# Slave_V0_1.net
KiCad netlist of a schematic drawn in EAGLE
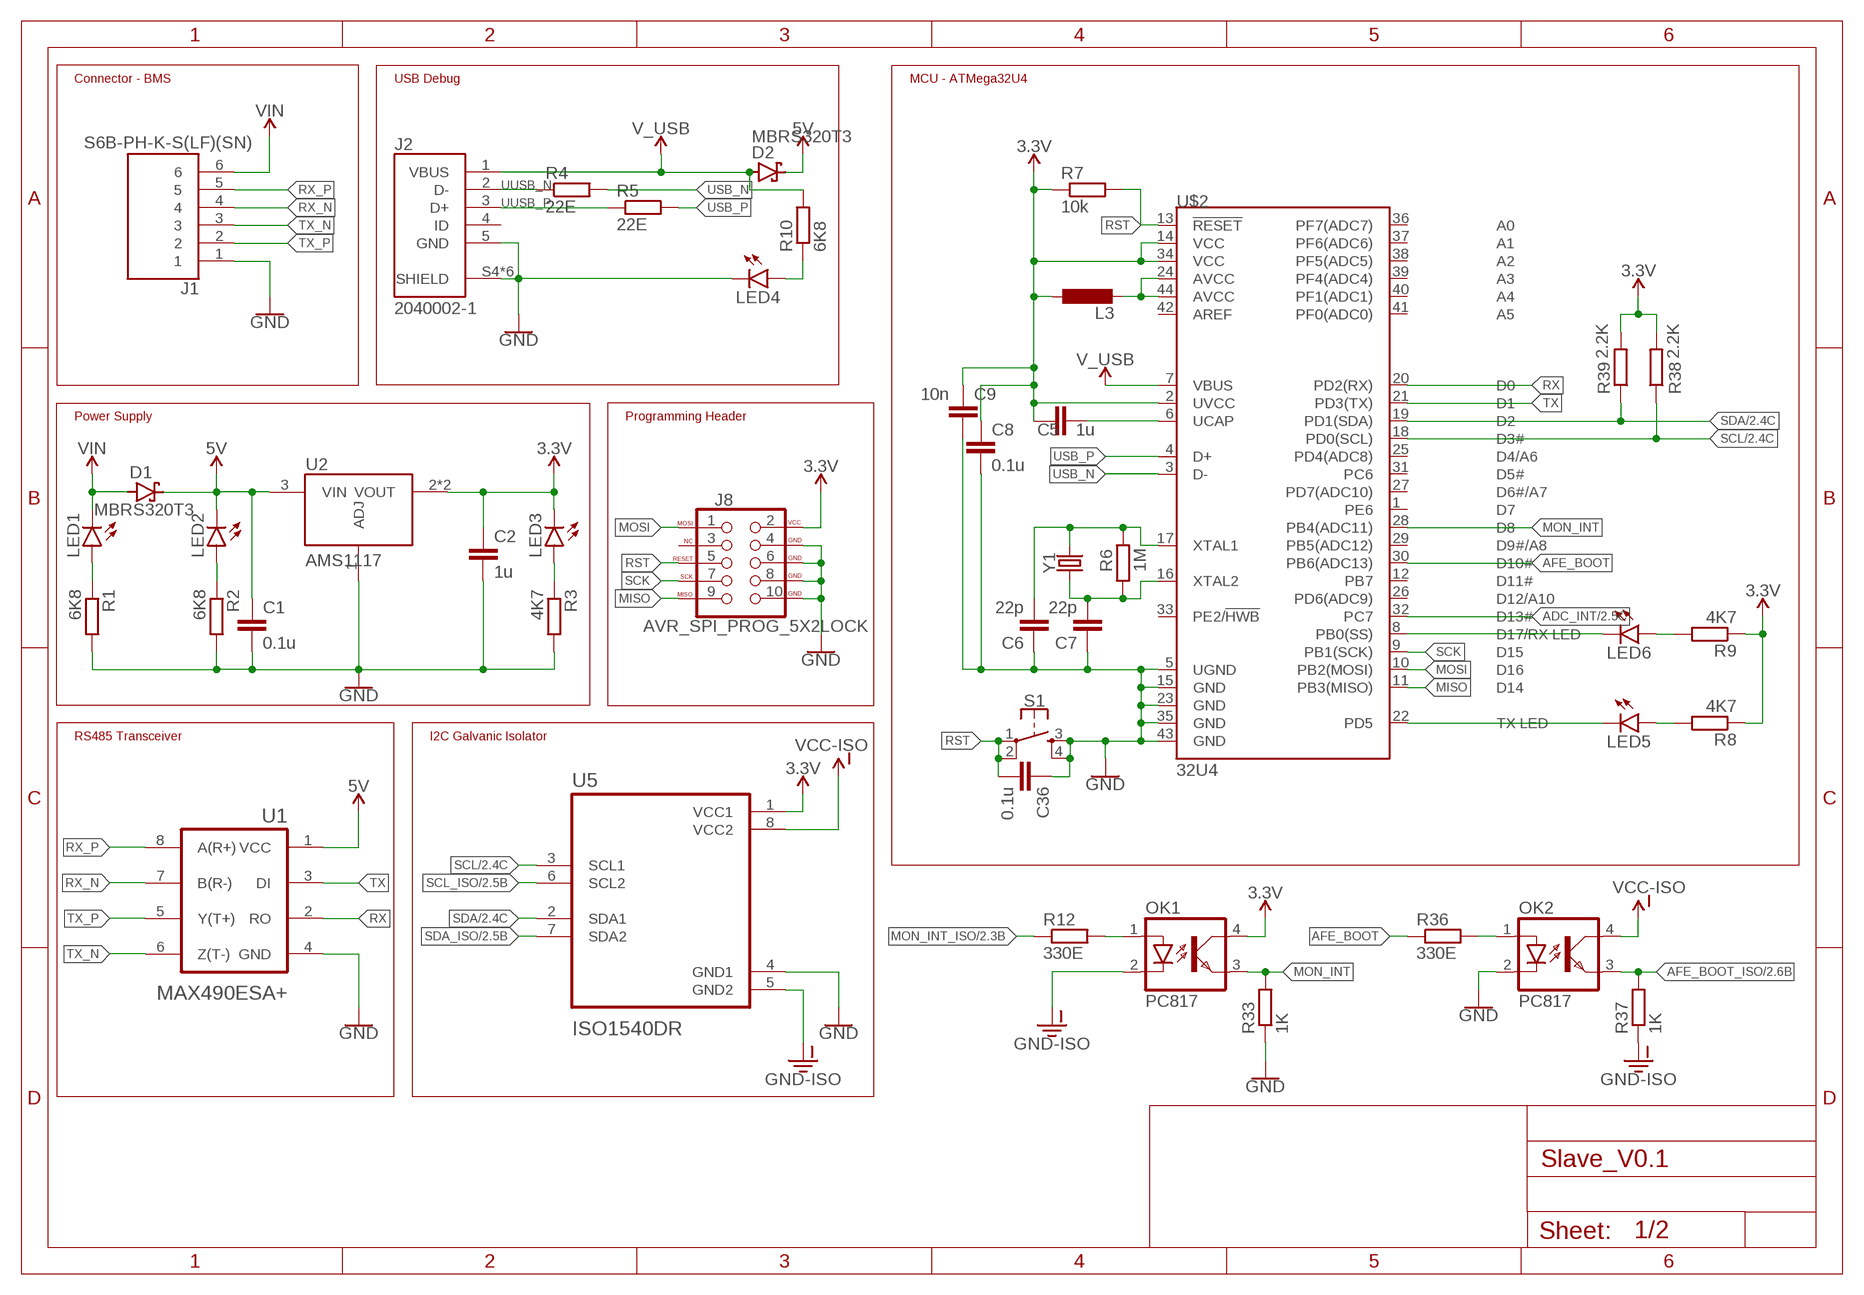
[diagram p0: schematic, sheet 1]
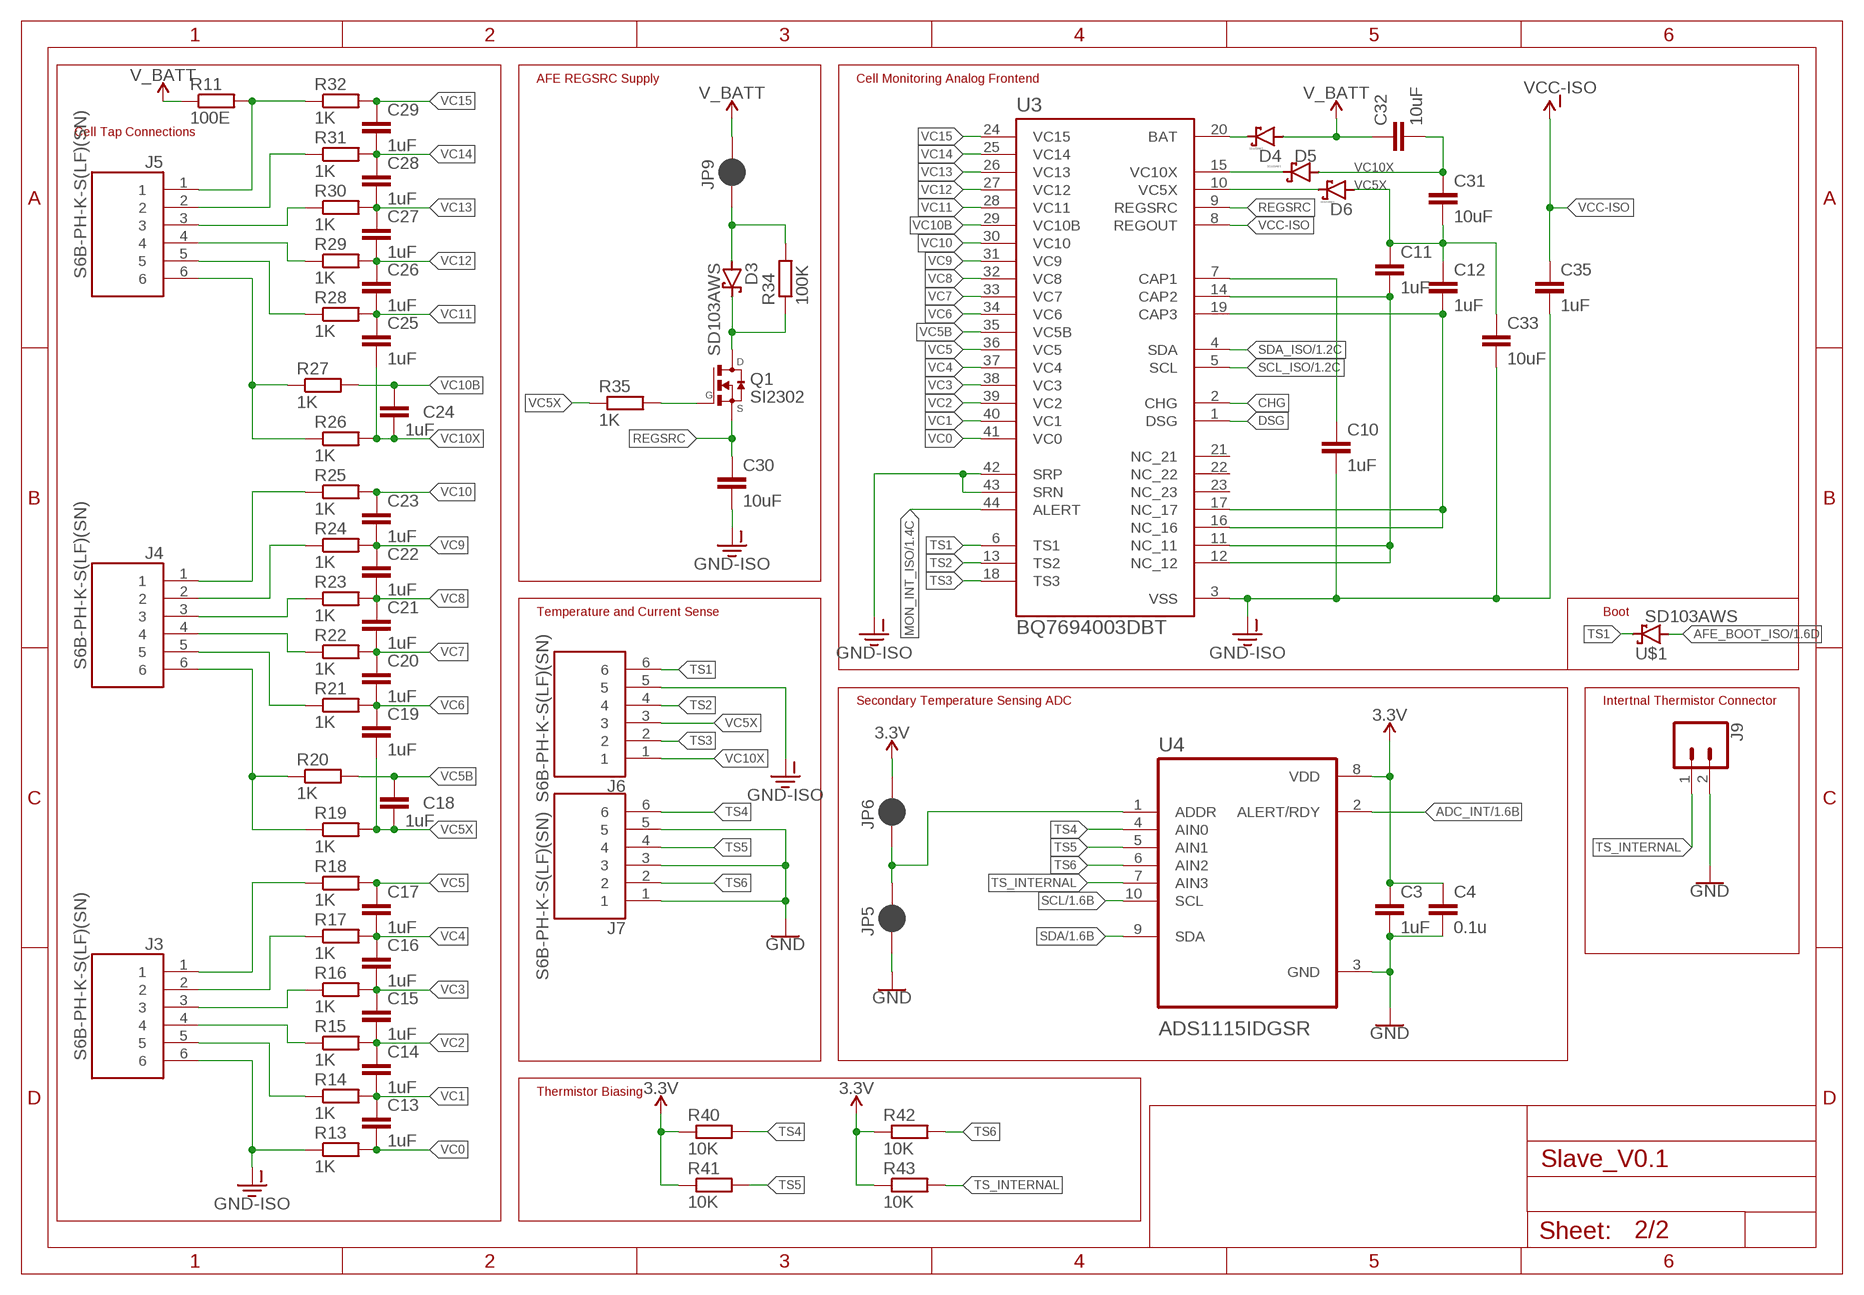
[diagram p1: schematic, sheet 2]

(export (version "E")
  (design (tool "Eeschema 10.0.6"))
  (components
    (comp (ref "C3")
      (value "1uF")
      (footprint "eagle-import:C0805K")
      (libsource (lib "eagle-import") (part "C-EUC0805K"))
    )
    (comp (ref "C4")
      (value "0.1u")
      (footprint "eagle-import:C0805K")
      (libsource (lib "eagle-import") (part "C-EUC0805K"))
    )
    (comp (ref "C10")
      (value "1uF")
      (footprint "eagle-import:C0805")
      (libsource (lib "eagle-import") (part "C-EUC0805"))
    )
    (comp (ref "C11")
      (value "1uF")
      (footprint "eagle-import:C0805")
      (libsource (lib "eagle-import") (part "C-EUC0805"))
    )
    (comp (ref "C12")
      (value "1uF")
      (footprint "eagle-import:C0805")
      (libsource (lib "eagle-import") (part "C-EUC0805"))
    )
    (comp (ref "C13")
      (value "1uF")
      (footprint "eagle-import:C0805")
      (libsource (lib "eagle-import") (part "C-EUC0805"))
    )
    (comp (ref "C14")
      (value "1uF")
      (footprint "eagle-import:C0805")
      (libsource (lib "eagle-import") (part "C-EUC0805"))
    )
    (comp (ref "C15")
      (value "1uF")
      (footprint "eagle-import:C0805")
      (libsource (lib "eagle-import") (part "C-EUC0805"))
    )
    (comp (ref "C16")
      (value "1uF")
      (footprint "eagle-import:C0805")
      (libsource (lib "eagle-import") (part "C-EUC0805"))
    )
    (comp (ref "C17")
      (value "1uF")
      (footprint "eagle-import:C0805")
      (libsource (lib "eagle-import") (part "C-EUC0805"))
    )
    (comp (ref "C18")
      (value "1uF")
      (footprint "eagle-import:C0805")
      (libsource (lib "eagle-import") (part "C-EUC0805"))
    )
    (comp (ref "C19")
      (value "1uF")
      (footprint "eagle-import:C0805")
      (libsource (lib "eagle-import") (part "C-EUC0805"))
    )
    (comp (ref "C20")
      (value "1uF")
      (footprint "eagle-import:C0805")
      (libsource (lib "eagle-import") (part "C-EUC0805"))
    )
    (comp (ref "C21")
      (value "1uF")
      (footprint "eagle-import:C0805")
      (libsource (lib "eagle-import") (part "C-EUC0805"))
    )
    (comp (ref "C22")
      (value "1uF")
      (footprint "eagle-import:C0805")
      (libsource (lib "eagle-import") (part "C-EUC0805"))
    )
    (comp (ref "C23")
      (value "1uF")
      (footprint "eagle-import:C0805")
      (libsource (lib "eagle-import") (part "C-EUC0805"))
    )
    (comp (ref "C24")
      (value "1uF")
      (footprint "eagle-import:C0805")
      (libsource (lib "eagle-import") (part "C-EUC0805"))
    )
    (comp (ref "C25")
      (value "1uF")
      (footprint "eagle-import:C0805")
      (libsource (lib "eagle-import") (part "C-EUC0805"))
    )
    (comp (ref "C26")
      (value "1uF")
      (footprint "eagle-import:C0805")
      (libsource (lib "eagle-import") (part "C-EUC0805"))
    )
    (comp (ref "C27")
      (value "1uF")
      (footprint "eagle-import:C0805")
      (libsource (lib "eagle-import") (part "C-EUC0805"))
    )
    (comp (ref "C28")
      (value "1uF")
      (footprint "eagle-import:C0805")
      (libsource (lib "eagle-import") (part "C-EUC0805"))
    )
    (comp (ref "C29")
      (value "1uF")
      (footprint "eagle-import:C0805")
      (libsource (lib "eagle-import") (part "C-EUC0805"))
    )
    (comp (ref "C30")
      (value "10uF")
      (footprint "eagle-import:C0805")
      (libsource (lib "eagle-import") (part "C-EUC0805"))
    )
    (comp (ref "C31")
      (value "10uF")
      (footprint "eagle-import:C0805")
      (libsource (lib "eagle-import") (part "C-EUC0805"))
    )
    (comp (ref "C32")
      (value "10uF")
      (footprint "eagle-import:C0805")
      (libsource (lib "eagle-import") (part "C-EUC0805"))
    )
    (comp (ref "C33")
      (value "10uF")
      (footprint "eagle-import:C0805")
      (libsource (lib "eagle-import") (part "C-EUC0805"))
    )
    (comp (ref "C35")
      (value "1uF")
      (footprint "eagle-import:C0805")
      (libsource (lib "eagle-import") (part "C-EUC0805"))
    )
    (comp (ref "D3")
      (value "SD103AWS")
      (footprint "eagle-import:SOD323_ST")
      (libsource (lib "eagle-import") (part "SD103AWS"))
    )
    (comp (ref "D4")
      (value "SD103AWS")
      (footprint "eagle-import:SOD323_ST")
      (libsource (lib "eagle-import") (part "SD103AWS"))
    )
    (comp (ref "D5")
      (value "SD103AWS")
      (footprint "eagle-import:SOD323_ST")
      (libsource (lib "eagle-import") (part "SD103AWS"))
    )
    (comp (ref "D6")
      (value "SD103AWS")
      (footprint "eagle-import:SOD323_ST")
      (libsource (lib "eagle-import") (part "SD103AWS"))
    )
    (comp (ref "J3")
      (value "S6B-PH-K-S(LF)(SN)")
      (footprint "eagle-import:JST_S6B-PH-K-S(LF)(SN)")
      (fields (field (name "MF") "JST Sales"))
      (libsource (lib "eagle-import") (part "S6B-PH-K-S(LF)(SN)"))
    )
    (comp (ref "J4")
      (value "S6B-PH-K-S(LF)(SN)")
      (footprint "eagle-import:JST_S6B-PH-K-S(LF)(SN)")
      (fields (field (name "MF") "JST Sales"))
      (libsource (lib "eagle-import") (part "S6B-PH-K-S(LF)(SN)"))
    )
    (comp (ref "J5")
      (value "S6B-PH-K-S(LF)(SN)")
      (footprint "eagle-import:JST_S6B-PH-K-S(LF)(SN)")
      (fields (field (name "MF") "JST Sales"))
      (libsource (lib "eagle-import") (part "S6B-PH-K-S(LF)(SN)"))
    )
    (comp (ref "J6")
      (value "S6B-PH-K-S(LF)(SN)")
      (footprint "eagle-import:JST_S6B-PH-K-S(LF)(SN)")
      (fields (field (name "MF") "JST Sales"))
      (libsource (lib "eagle-import") (part "S6B-PH-K-S(LF)(SN)"))
    )
    (comp (ref "J7")
      (value "S6B-PH-K-S(LF)(SN)")
      (footprint "eagle-import:JST_S6B-PH-K-S(LF)(SN)")
      (fields (field (name "MF") "JST Sales"))
      (libsource (lib "eagle-import") (part "S6B-PH-K-S(LF)(SN)"))
    )
    (comp (ref "J9")
      (value "CONN_023.5MM-NO_SILK")
      (footprint "eagle-import:SCREWTERMINAL-3.5MM-2-NS")
      (libsource (lib "eagle-import") (part "CONN_023.5MM-NO_SILK"))
    )
    (comp (ref "JP5")
      (value "JUMPER-SMT_2_NC_PASTE_SILK")
      (footprint "eagle-import:SMT-JUMPER_2_NC_PASTE_SILK")
      (libsource (lib "eagle-import") (part "JUMPER-SMT_2_NC_PASTE_SILK"))
    )
    (comp (ref "JP6")
      (value "JUMPER-SMT_2_NC_PASTE_SILK")
      (footprint "eagle-import:SMT-JUMPER_2_NC_PASTE_SILK")
      (libsource (lib "eagle-import") (part "JUMPER-SMT_2_NC_PASTE_SILK"))
    )
    (comp (ref "JP9")
      (value "JUMPER-SMT_2_NC_PASTE_SILK")
      (footprint "eagle-import:SMT-JUMPER_2_NC_PASTE_SILK")
      (libsource (lib "eagle-import") (part "JUMPER-SMT_2_NC_PASTE_SILK"))
    )
    (comp (ref "Q1")
      (value "SI2302")
      (footprint "eagle-import:SOT23")
      (fields (field (name "MF") "Vishay Siliconix"))
      (libsource (lib "eagle-import") (part "SI2302"))
    )
    (comp (ref "R11")
      (value "100E")
      (footprint "eagle-import:R0805")
      (libsource (lib "eagle-import") (part "R-EU_R0805"))
    )
    (comp (ref "R13")
      (value "1K")
      (footprint "eagle-import:R0805")
      (libsource (lib "eagle-import") (part "R-EU_R0805"))
    )
    (comp (ref "R14")
      (value "1K")
      (footprint "eagle-import:R0805")
      (libsource (lib "eagle-import") (part "R-EU_R0805"))
    )
    (comp (ref "R15")
      (value "1K")
      (footprint "eagle-import:R0805")
      (libsource (lib "eagle-import") (part "R-EU_R0805"))
    )
    (comp (ref "R16")
      (value "1K")
      (footprint "eagle-import:R0805")
      (libsource (lib "eagle-import") (part "R-EU_R0805"))
    )
    (comp (ref "R17")
      (value "1K")
      (footprint "eagle-import:R0805")
      (libsource (lib "eagle-import") (part "R-EU_R0805"))
    )
    (comp (ref "R18")
      (value "1K")
      (footprint "eagle-import:R0805")
      (libsource (lib "eagle-import") (part "R-EU_R0805"))
    )
    (comp (ref "R19")
      (value "1K")
      (footprint "eagle-import:R0805")
      (libsource (lib "eagle-import") (part "R-EU_R0805"))
    )
    (comp (ref "R20")
      (value "1K")
      (footprint "eagle-import:R0805")
      (libsource (lib "eagle-import") (part "R-EU_R0805"))
    )
    (comp (ref "R21")
      (value "1K")
      (footprint "eagle-import:R0805")
      (libsource (lib "eagle-import") (part "R-EU_R0805"))
    )
    (comp (ref "R22")
      (value "1K")
      (footprint "eagle-import:R0805")
      (libsource (lib "eagle-import") (part "R-EU_R0805"))
    )
    (comp (ref "R23")
      (value "1K")
      (footprint "eagle-import:R0805")
      (libsource (lib "eagle-import") (part "R-EU_R0805"))
    )
    (comp (ref "R24")
      (value "1K")
      (footprint "eagle-import:R0805")
      (libsource (lib "eagle-import") (part "R-EU_R0805"))
    )
    (comp (ref "R25")
      (value "1K")
      (footprint "eagle-import:R0805")
      (libsource (lib "eagle-import") (part "R-EU_R0805"))
    )
    (comp (ref "R26")
      (value "1K")
      (footprint "eagle-import:R0805")
      (libsource (lib "eagle-import") (part "R-EU_R0805"))
    )
    (comp (ref "R27")
      (value "1K")
      (footprint "eagle-import:R0805")
      (libsource (lib "eagle-import") (part "R-EU_R0805"))
    )
    (comp (ref "R28")
      (value "1K")
      (footprint "eagle-import:R0805")
      (libsource (lib "eagle-import") (part "R-EU_R0805"))
    )
    (comp (ref "R29")
      (value "1K")
      (footprint "eagle-import:R0805")
      (libsource (lib "eagle-import") (part "R-EU_R0805"))
    )
    (comp (ref "R30")
      (value "1K")
      (footprint "eagle-import:R0805")
      (libsource (lib "eagle-import") (part "R-EU_R0805"))
    )
    (comp (ref "R31")
      (value "1K")
      (footprint "eagle-import:R0805")
      (libsource (lib "eagle-import") (part "R-EU_R0805"))
    )
    (comp (ref "R32")
      (value "1K")
      (footprint "eagle-import:R0805")
      (libsource (lib "eagle-import") (part "R-EU_R0805"))
    )
    (comp (ref "R34")
      (value "100K")
      (footprint "eagle-import:R0805")
      (libsource (lib "eagle-import") (part "R-EU_R0805"))
    )
    (comp (ref "R35")
      (value "1K")
      (footprint "eagle-import:R0805")
      (libsource (lib "eagle-import") (part "R-EU_R0805"))
    )
    (comp (ref "R40")
      (value "10K")
      (footprint "eagle-import:R0805")
      (libsource (lib "eagle-import") (part "R-EU_R0805"))
    )
    (comp (ref "R41")
      (value "10K")
      (footprint "eagle-import:R0805")
      (libsource (lib "eagle-import") (part "R-EU_R0805"))
    )
    (comp (ref "R42")
      (value "10K")
      (footprint "eagle-import:R0805")
      (libsource (lib "eagle-import") (part "R-EU_R0805"))
    )
    (comp (ref "R43")
      (value "10K")
      (footprint "eagle-import:R0805")
      (libsource (lib "eagle-import") (part "R-EU_R0805"))
    )
    (comp (ref "U$1")
      (value "SD103AWS")
      (footprint "eagle-import:SOD323_ST")
      (libsource (lib "eagle-import") (part "SD103AWS"))
    )
    (comp (ref "U3")
      (value "BQ7694003DBT")
      (footprint "eagle-import:SOP50P640X120-44N")
      (fields (field (name "MF") "Texas Instruments"))
      (libsource (lib "eagle-import") (part "BQ7694003DBT"))
    )
    (comp (ref "U4")
      (value "ADS1115IDGSR")
      (footprint "eagle-import:SOP50P490X110-10N")
      (fields (field (name "MF") "Texas Instruments"))
      (libsource (lib "eagle-import") (part "ADS1115IDGSR"))
    )
    (comp (ref "C1")
      (value "0.1u")
      (footprint "eagle-import:C0805")
      (libsource (lib "eagle-import") (part "C-EUC0805"))
    )
    (comp (ref "C2")
      (value "1u")
      (footprint "eagle-import:C0805")
      (libsource (lib "eagle-import") (part "C-EUC0805"))
    )
    (comp (ref "C5")
      (value "1u")
      (footprint "eagle-import:C0805")
      (libsource (lib "eagle-import") (part "C-EUC0805"))
    )
    (comp (ref "C6")
      (value "22p")
      (footprint "eagle-import:C0805")
      (libsource (lib "eagle-import") (part "C-EUC0805"))
    )
    (comp (ref "C7")
      (value "22p")
      (footprint "eagle-import:C0805")
      (libsource (lib "eagle-import") (part "C-EUC0805"))
    )
    (comp (ref "C8")
      (value "0.1u")
      (footprint "eagle-import:C0805")
      (libsource (lib "eagle-import") (part "C-EUC0805"))
    )
    (comp (ref "C9")
      (value "10n")
      (footprint "eagle-import:C0805")
      (libsource (lib "eagle-import") (part "C-EUC0805"))
    )
    (comp (ref "C36")
      (value "0.1u")
      (footprint "eagle-import:C0805")
      (libsource (lib "eagle-import") (part "C-EUC0805"))
    )
    (comp (ref "D1")
      (value "MBRS320T3")
      (footprint "eagle-import:SMC")
      (libsource (lib "eagle-import") (part "MBRS30T32"))
    )
    (comp (ref "D2")
      (value "MBRS320T3")
      (footprint "eagle-import:SMC")
      (libsource (lib "eagle-import") (part "MBRS30T32"))
    )
    (comp (ref "J1")
      (value "S6B-PH-K-S(LF)(SN)")
      (footprint "eagle-import:JST_S6B-PH-K-S(LF)(SN)")
      (fields (field (name "MF") "JST Sales"))
      (libsource (lib "eagle-import") (part "S6B-PH-K-S(LF)(SN)"))
    )
    (comp (ref "J2")
      (value "2040002-1")
      (footprint "eagle-import:TE_2040002-1")
      (fields (field (name "MF") "TE Connectivity"))
      (libsource (lib "eagle-import") (part "2040002-1"))
    )
    (comp (ref "J8")
      (value "AVR_SPI_PROG_5X2LOCK")
      (footprint "eagle-import:2X5-SHROUDED_LOCK")
      (libsource (lib "eagle-import") (part "AVR_SPI_PROG_5X2LOCK"))
    )
    (comp (ref "L3")
      (value "L-EUL2012C")
      (footprint "eagle-import:L2012C")
      (libsource (lib "eagle-import") (part "L-EUL2012C"))
    )
    (comp (ref "LED1")
      (value "LEDCHIPLED_0805")
      (footprint "eagle-import:CHIPLED_0805")
      (libsource (lib "eagle-import") (part "LEDCHIPLED_0805"))
    )
    (comp (ref "LED2")
      (value "LEDCHIPLED_0805")
      (footprint "eagle-import:CHIPLED_0805")
      (libsource (lib "eagle-import") (part "LEDCHIPLED_0805"))
    )
    (comp (ref "LED3")
      (value "LEDCHIPLED_0805")
      (footprint "eagle-import:CHIPLED_0805")
      (libsource (lib "eagle-import") (part "LEDCHIPLED_0805"))
    )
    (comp (ref "LED4")
      (value "LEDCHIPLED_0805")
      (footprint "eagle-import:CHIPLED_0805")
      (libsource (lib "eagle-import") (part "LEDCHIPLED_0805"))
    )
    (comp (ref "LED5")
      (value "LEDCHIPLED_0805")
      (footprint "eagle-import:CHIPLED_0805")
      (libsource (lib "eagle-import") (part "LEDCHIPLED_0805"))
    )
    (comp (ref "LED6")
      (value "LEDCHIPLED_0805")
      (footprint "eagle-import:CHIPLED_0805")
      (libsource (lib "eagle-import") (part "LEDCHIPLED_0805"))
    )
    (comp (ref "OK1")
      (value "PC817")
      (footprint "eagle-import:DIL04")
      (fields (field (name "MPN") "PC817X4J000F"))
      (libsource (lib "eagle-import") (part "PC817"))
    )
    (comp (ref "OK2")
      (value "PC817")
      (footprint "eagle-import:DIL04")
      (fields (field (name "MPN") "PC817X4J000F"))
      (libsource (lib "eagle-import") (part "PC817"))
    )
    (comp (ref "R1")
      (value "6K8")
      (footprint "eagle-import:R0805")
      (libsource (lib "eagle-import") (part "R-EU_R0805"))
    )
    (comp (ref "R2")
      (value "6K8")
      (footprint "eagle-import:R0805")
      (libsource (lib "eagle-import") (part "R-EU_R0805"))
    )
    (comp (ref "R3")
      (value "4K7")
      (footprint "eagle-import:R0805")
      (libsource (lib "eagle-import") (part "R-EU_R0805"))
    )
    (comp (ref "R4")
      (value "22E")
      (footprint "eagle-import:R0805")
      (libsource (lib "eagle-import") (part "R-EU_R0805"))
    )
    (comp (ref "R5")
      (value "22E")
      (footprint "eagle-import:R0805")
      (libsource (lib "eagle-import") (part "R-EU_R0805"))
    )
    (comp (ref "R6")
      (value "1M")
      (footprint "eagle-import:R0805")
      (libsource (lib "eagle-import") (part "R-EU_R0805"))
    )
    (comp (ref "R7")
      (value "10k")
      (footprint "eagle-import:R0805")
      (libsource (lib "eagle-import") (part "R-EU_R0805"))
    )
    (comp (ref "R8")
      (value "4K7")
      (footprint "eagle-import:R0805")
      (libsource (lib "eagle-import") (part "R-EU_R0805"))
    )
    (comp (ref "R9")
      (value "4K7")
      (footprint "eagle-import:R0805")
      (libsource (lib "eagle-import") (part "R-EU_R0805"))
    )
    (comp (ref "R10")
      (value "6K8")
      (footprint "eagle-import:R0805")
      (libsource (lib "eagle-import") (part "R-EU_R0805"))
    )
    (comp (ref "R12")
      (value "330E")
      (footprint "eagle-import:R0805")
      (libsource (lib "eagle-import") (part "R-EU_R0805"))
    )
    (comp (ref "R33")
      (value "1K")
      (footprint "eagle-import:R0805")
      (libsource (lib "eagle-import") (part "R-EU_R0805"))
    )
    (comp (ref "R36")
      (value "330E")
      (footprint "eagle-import:R0805")
      (libsource (lib "eagle-import") (part "R-EU_R0805"))
    )
    (comp (ref "R37")
      (value "1K")
      (footprint "eagle-import:R0805")
      (libsource (lib "eagle-import") (part "R-EU_R0805"))
    )
    (comp (ref "R38")
      (value "2.2K")
      (footprint "eagle-import:R0805")
      (libsource (lib "eagle-import") (part "R-EU_R0805"))
    )
    (comp (ref "R39")
      (value "2.2K")
      (footprint "eagle-import:R0805")
      (libsource (lib "eagle-import") (part "R-EU_R0805"))
    )
    (comp (ref "S1")
      (value "MOMENTARY-SWITCH-SPST-2-SMD-5.2MM")
      (footprint "eagle-import:TACTILE_SWITCH_SMD_5.2MM")
      (libsource (lib "eagle-import") (part "MOMENTARY-SWITCH-SPST-2-SMD-5.2MM"))
    )
    (comp (ref "U$2")
      (value "32U4")
      (footprint "eagle-import:TQFP44")
      (libsource (lib "eagle-import") (part "ATMEGA32U4TQFP-44"))
    )
    (comp (ref "U1")
      (value "MAX490ESA+")
      (footprint "eagle-import:SOIC127P600X175-8N")
      (fields (field (name "MF") "Maxim Integrated"))
      (libsource (lib "eagle-import") (part "MAX490ESA+"))
    )
    (comp (ref "U2")
      (value "AMS1117")
      (footprint "eagle-import:SOT230P700X170-4")
      (fields (field (name "MF") "Advanced Monolithic Systems, Inc."))
      (libsource (lib "eagle-import") (part "AMS1117"))
    )
    (comp (ref "U5")
      (value "ISO1540DR")
      (footprint "eagle-import:SOIC127P599X175-8N")
      (fields (field (name "MF") "Texas Instruments"))
      (libsource (lib "eagle-import") (part "ISO1540DR"))
    )
    (comp (ref "Y1")
      (value "CRYSTALPTH-HC49UV")
      (footprint "eagle-import:HC49U")
      (libsource (lib "eagle-import") (part "CRYSTALPTH-HC49UV"))
    )
  )
  (nets
    (net (code "1") (name "3.3V") (class "Default")
      (node (ref "C2") (pin "1") (pinfunction "1_1") (pintype "passive"))
      (node (ref "C3") (pin "1") (pinfunction "1_1") (pintype "passive"))
      (node (ref "C4") (pin "1") (pinfunction "1_1") (pintype "passive"))
      (node (ref "C5") (pin "1") (pinfunction "1_1") (pintype "passive"))
      (node (ref "C8") (pin "1") (pinfunction "1_1") (pintype "passive"))
      (node (ref "C9") (pin "1") (pinfunction "1_1") (pintype "passive"))
      (node (ref "J8") (pin "2") (pinfunction "VCC_2") (pintype "power_in"))
      (node (ref "JP6") (pin "2") (pinfunction "2_2") (pintype "passive"))
      (node (ref "L3") (pin "1") (pinfunction "1_1") (pintype "passive"))
      (node (ref "LED3") (pin "C") (pinfunction "C_C") (pintype "passive"))
      (node (ref "OK1") (pin "4") (pinfunction "COL_4") (pintype "passive"))
      (node (ref "R38") (pin "2") (pinfunction "2_2") (pintype "passive"))
      (node (ref "R39") (pin "2") (pinfunction "2_2") (pintype "passive"))
      (node (ref "R40") (pin "1") (pinfunction "1_1") (pintype "passive"))
      (node (ref "R41") (pin "1") (pinfunction "1_1") (pintype "passive"))
      (node (ref "R42") (pin "1") (pinfunction "1_1") (pintype "passive"))
      (node (ref "R43") (pin "1") (pinfunction "1_1") (pintype "passive"))
      (node (ref "R7") (pin "1") (pinfunction "1_1") (pintype "passive"))
      (node (ref "R8") (pin "1") (pinfunction "1_1") (pintype "passive"))
      (node (ref "R9") (pin "1") (pinfunction "1_1") (pintype "passive"))
      (node (ref "U$2") (pin "14") (pinfunction "VCC_14") (pintype "bidirectional"))
      (node (ref "U$2") (pin "2") (pinfunction "UVCC_2") (pintype "bidirectional"))
      (node (ref "U$2") (pin "34") (pinfunction "VCC_34") (pintype "bidirectional"))
      (node (ref "U2") (pin "2") (pinfunction "VOUT_2") (pintype "output"))
      (node (ref "U2") (pin "4") (pinfunction "VOUT_4") (pintype "output"))
      (node (ref "U4") (pin "8") (pinfunction "VDD_8") (pintype "power_in"))
      (node (ref "U5") (pin "1") (pinfunction "VCC1_1") (pintype "power_in"))
    )
    (net (code "2") (name "5V") (class "Default")
      (node (ref "C1") (pin "1") (pinfunction "1_1") (pintype "passive"))
      (node (ref "D1") (pin "C") (pinfunction "C_C") (pintype "passive"))
      (node (ref "D2") (pin "C") (pinfunction "C_C") (pintype "passive"))
      (node (ref "LED2") (pin "C") (pinfunction "C_C") (pintype "passive"))
      (node (ref "U1") (pin "1") (pinfunction "VCC_1") (pintype "power_in"))
      (node (ref "U2") (pin "3") (pinfunction "VIN_3") (pintype "input"))
    )
    (net (code "3") (name "ADC_INT") (class "Default")
      (node (ref "U$2") (pin "32") (pinfunction "PC7_32") (pintype "bidirectional"))
      (node (ref "U4") (pin "2") (pinfunction "ALERT/RDY_2") (pintype "output"))
    )
    (net (code "4") (name "AFE_BOOT") (class "Default")
      (node (ref "R36") (pin "1") (pinfunction "1_1") (pintype "passive"))
      (node (ref "U$2") (pin "30") (pinfunction "PB6(ADC13)_30") (pintype "bidirectional"))
    )
    (net (code "5") (name "AFE_BOOT_ISO") (class "Default")
      (node (ref "OK2") (pin "3") (pinfunction "EMIT_3") (pintype "passive"))
      (node (ref "R37") (pin "2") (pinfunction "2_2") (pintype "passive"))
      (node (ref "U$1") (pin "A") (pinfunction "A_A") (pintype "passive"))
    )
    (net (code "6") (name "CHG") (class "Default")
      (node (ref "U3") (pin "2") (pinfunction "CHG_2") (pintype "output"))
    )
    (net (code "7") (name "DSG") (class "Default")
      (node (ref "U3") (pin "1") (pinfunction "DSG_1") (pintype "output"))
    )
    (net (code "8") (name "GND") (class "Default")
      (node (ref "C1") (pin "2") (pinfunction "2_2") (pintype "passive"))
      (node (ref "C2") (pin "2") (pinfunction "2_2") (pintype "passive"))
      (node (ref "C3") (pin "2") (pinfunction "2_2") (pintype "passive"))
      (node (ref "C36") (pin "1") (pinfunction "1_1") (pintype "passive"))
      (node (ref "C4") (pin "2") (pinfunction "2_2") (pintype "passive"))
      (node (ref "C6") (pin "1") (pinfunction "1_1") (pintype "passive"))
      (node (ref "C7") (pin "1") (pinfunction "1_1") (pintype "passive"))
      (node (ref "C8") (pin "2") (pinfunction "2_2") (pintype "passive"))
      (node (ref "C9") (pin "2") (pinfunction "2_2") (pintype "passive"))
      (node (ref "J1") (pin "1") (pinfunction "1_1") (pintype "passive"))
      (node (ref "J2") (pin "5") (pinfunction "GND_5") (pintype "power_in"))
      (node (ref "J2") (pin "S4") (pinfunction "SHIELD_S4") (pintype "power_in"))
      (node (ref "J2") (pin "S5") (pinfunction "SHIELD_S5") (pintype "power_in"))
      (node (ref "J2") (pin "SH1") (pinfunction "SHIELD_SH1") (pintype "power_in"))
      (node (ref "J2") (pin "SH2") (pinfunction "SHIELD_SH2") (pintype "power_in"))
      (node (ref "J2") (pin "SH3") (pinfunction "SHIELD_SH3") (pintype "power_in"))
      (node (ref "J2") (pin "SH4") (pinfunction "SHIELD_SH4") (pintype "power_in"))
      (node (ref "J7") (pin "1") (pinfunction "1_1") (pintype "passive"))
      (node (ref "J7") (pin "3") (pinfunction "3_3") (pintype "passive"))
      (node (ref "J7") (pin "5") (pinfunction "5_5") (pintype "passive"))
      (node (ref "J8") (pin "10") (pinfunction "GND_10") (pintype "power_in"))
      (node (ref "J8") (pin "4") (pinfunction "GND_4") (pintype "power_in"))
      (node (ref "J8") (pin "6") (pinfunction "GND_6") (pintype "power_in"))
      (node (ref "J8") (pin "8") (pinfunction "GND_8") (pintype "power_in"))
      (node (ref "J9") (pin "2") (pinfunction "2_2") (pintype "passive"))
      (node (ref "JP5") (pin "1") (pinfunction "1_1") (pintype "passive"))
      (node (ref "LED4") (pin "C") (pinfunction "C_C") (pintype "passive"))
      (node (ref "OK2") (pin "2") (pinfunction "C_2") (pintype "passive"))
      (node (ref "R1") (pin "2") (pinfunction "2_2") (pintype "passive"))
      (node (ref "R2") (pin "2") (pinfunction "2_2") (pintype "passive"))
      (node (ref "R3") (pin "2") (pinfunction "2_2") (pintype "passive"))
      (node (ref "R33") (pin "1") (pinfunction "1_1") (pintype "passive"))
      (node (ref "S1") (pin "3") (pinfunction "3_3") (pintype "passive"))
      (node (ref "S1") (pin "4") (pinfunction "4_4") (pintype "passive"))
      (node (ref "U$2") (pin "15") (pinfunction "GND_15") (pintype "bidirectional"))
      (node (ref "U$2") (pin "23") (pinfunction "GND_23") (pintype "bidirectional"))
      (node (ref "U$2") (pin "35") (pinfunction "GND_35") (pintype "bidirectional"))
      (node (ref "U$2") (pin "43") (pinfunction "GND_43") (pintype "bidirectional"))
      (node (ref "U$2") (pin "5") (pinfunction "UGND_5") (pintype "bidirectional"))
      (node (ref "U1") (pin "4") (pinfunction "GND_4") (pintype "power_in"))
      (node (ref "U2") (pin "1") (pinfunction "ADJ_1") (pintype "power_in"))
      (node (ref "U4") (pin "3") (pinfunction "GND_3") (pintype "power_in"))
      (node (ref "U5") (pin "4") (pinfunction "GND1_4") (pintype "power_in"))
    )
    (net (code "9") (name "GND-ISO") (class "Default")
      (node (ref "C10") (pin "2") (pinfunction "2_2") (pintype "passive"))
      (node (ref "C30") (pin "2") (pinfunction "2_2") (pintype "passive"))
      (node (ref "C33") (pin "2") (pinfunction "2_2") (pintype "passive"))
      (node (ref "C35") (pin "2") (pinfunction "2_2") (pintype "passive"))
      (node (ref "J3") (pin "6") (pinfunction "6_6") (pintype "passive"))
      (node (ref "J6") (pin "5") (pinfunction "5_5") (pintype "passive"))
      (node (ref "OK1") (pin "2") (pinfunction "C_2") (pintype "passive"))
      (node (ref "R13") (pin "1") (pinfunction "1_1") (pintype "passive"))
      (node (ref "R37") (pin "1") (pinfunction "1_1") (pintype "passive"))
      (node (ref "U3") (pin "3") (pinfunction "VSS_3") (pintype "power_in"))
      (node (ref "U3") (pin "42") (pinfunction "SRP_42") (pintype "input"))
      (node (ref "U3") (pin "43") (pinfunction "SRN_43") (pintype "input"))
      (node (ref "U5") (pin "5") (pinfunction "GND2_5") (pintype "power_in"))
    )
    (net (code "10") (name "MISO") (class "Default")
      (node (ref "J8") (pin "9") (pinfunction "MISO_9") (pintype "passive"))
      (node (ref "U$2") (pin "11") (pinfunction "PB3(MISO)_11") (pintype "bidirectional"))
    )
    (net (code "11") (name "MON_INT") (class "Default")
      (node (ref "OK1") (pin "3") (pinfunction "EMIT_3") (pintype "passive"))
      (node (ref "R33") (pin "2") (pinfunction "2_2") (pintype "passive"))
      (node (ref "U$2") (pin "28") (pinfunction "PB4(ADC11)_28") (pintype "bidirectional"))
    )
    (net (code "12") (name "MON_INT_ISO") (class "Default")
      (node (ref "R12") (pin "1") (pinfunction "1_1") (pintype "passive"))
      (node (ref "U3") (pin "44") (pinfunction "ALERT_44") (pintype "bidirectional"))
    )
    (net (code "13") (name "MOSI") (class "Default")
      (node (ref "J8") (pin "1") (pinfunction "MOSI_1") (pintype "passive"))
      (node (ref "U$2") (pin "10") (pinfunction "PB2(MOSI)_10") (pintype "bidirectional"))
    )
    (net (code "14") (name "Net-(D3-PadA)") (class "Default")
      (node (ref "D3") (pin "A") (pinfunction "A_A") (pintype "passive"))
      (node (ref "JP9") (pin "1") (pinfunction "1_1") (pintype "passive"))
      (node (ref "R34") (pin "2") (pinfunction "2_2") (pintype "passive"))
    )
    (net (code "15") (name "Net-(J3-Pad1)") (class "Default")
      (node (ref "J3") (pin "1") (pinfunction "1_1") (pintype "passive"))
      (node (ref "R18") (pin "1") (pinfunction "1_1") (pintype "passive"))
    )
    (net (code "16") (name "Net-(J3-Pad2)") (class "Default")
      (node (ref "J3") (pin "2") (pinfunction "2_2") (pintype "passive"))
      (node (ref "R17") (pin "1") (pinfunction "1_1") (pintype "passive"))
    )
    (net (code "17") (name "Net-(J3-Pad3)") (class "Default")
      (node (ref "J3") (pin "3") (pinfunction "3_3") (pintype "passive"))
      (node (ref "R16") (pin "1") (pinfunction "1_1") (pintype "passive"))
    )
    (net (code "18") (name "Net-(J3-Pad4)") (class "Default")
      (node (ref "J3") (pin "4") (pinfunction "4_4") (pintype "passive"))
      (node (ref "R15") (pin "1") (pinfunction "1_1") (pintype "passive"))
    )
    (net (code "19") (name "Net-(J3-Pad5)") (class "Default")
      (node (ref "J3") (pin "5") (pinfunction "5_5") (pintype "passive"))
      (node (ref "R14") (pin "1") (pinfunction "1_1") (pintype "passive"))
    )
    (net (code "20") (name "Net-(J4-Pad1)") (class "Default")
      (node (ref "J4") (pin "1") (pinfunction "1_1") (pintype "passive"))
      (node (ref "R25") (pin "1") (pinfunction "1_1") (pintype "passive"))
    )
    (net (code "21") (name "Net-(J4-Pad2)") (class "Default")
      (node (ref "J4") (pin "2") (pinfunction "2_2") (pintype "passive"))
      (node (ref "R24") (pin "1") (pinfunction "1_1") (pintype "passive"))
    )
    (net (code "22") (name "Net-(J4-Pad3)") (class "Default")
      (node (ref "J4") (pin "3") (pinfunction "3_3") (pintype "passive"))
      (node (ref "R23") (pin "1") (pinfunction "1_1") (pintype "passive"))
    )
    (net (code "23") (name "Net-(J4-Pad4)") (class "Default")
      (node (ref "J4") (pin "4") (pinfunction "4_4") (pintype "passive"))
      (node (ref "R22") (pin "1") (pinfunction "1_1") (pintype "passive"))
    )
    (net (code "24") (name "Net-(J4-Pad5)") (class "Default")
      (node (ref "J4") (pin "5") (pinfunction "5_5") (pintype "passive"))
      (node (ref "R21") (pin "1") (pinfunction "1_1") (pintype "passive"))
    )
    (net (code "25") (name "Net-(J4-Pad6)") (class "Default")
      (node (ref "J4") (pin "6") (pinfunction "6_6") (pintype "passive"))
      (node (ref "R19") (pin "1") (pinfunction "1_1") (pintype "passive"))
      (node (ref "R20") (pin "1") (pinfunction "1_1") (pintype "passive"))
    )
    (net (code "26") (name "Net-(J5-Pad1)") (class "Default")
      (node (ref "J5") (pin "1") (pinfunction "1_1") (pintype "passive"))
      (node (ref "R11") (pin "2") (pinfunction "2_2") (pintype "passive"))
      (node (ref "R32") (pin "1") (pinfunction "1_1") (pintype "passive"))
    )
    (net (code "27") (name "Net-(J5-Pad2)") (class "Default")
      (node (ref "J5") (pin "2") (pinfunction "2_2") (pintype "passive"))
      (node (ref "R31") (pin "1") (pinfunction "1_1") (pintype "passive"))
    )
    (net (code "28") (name "Net-(J5-Pad3)") (class "Default")
      (node (ref "J5") (pin "3") (pinfunction "3_3") (pintype "passive"))
      (node (ref "R30") (pin "1") (pinfunction "1_1") (pintype "passive"))
    )
    (net (code "29") (name "Net-(J5-Pad4)") (class "Default")
      (node (ref "J5") (pin "4") (pinfunction "4_4") (pintype "passive"))
      (node (ref "R29") (pin "1") (pinfunction "1_1") (pintype "passive"))
    )
    (net (code "30") (name "Net-(J5-Pad5)") (class "Default")
      (node (ref "J5") (pin "5") (pinfunction "5_5") (pintype "passive"))
      (node (ref "R28") (pin "1") (pinfunction "1_1") (pintype "passive"))
    )
    (net (code "31") (name "Net-(J5-Pad6)") (class "Default")
      (node (ref "J5") (pin "6") (pinfunction "6_6") (pintype "passive"))
      (node (ref "R26") (pin "1") (pinfunction "1_1") (pintype "passive"))
      (node (ref "R27") (pin "1") (pinfunction "1_1") (pintype "passive"))
    )
    (net (code "32") (name "Net-(L3-Pad2)") (class "Default")
      (node (ref "L3") (pin "2") (pinfunction "2_2") (pintype "passive"))
      (node (ref "U$2") (pin "24") (pinfunction "AVCC_24") (pintype "bidirectional"))
      (node (ref "U$2") (pin "44") (pinfunction "AVCC_44") (pintype "bidirectional"))
    )
    (net (code "33") (name "Net-(LED1-PadA)") (class "Default")
      (node (ref "LED1") (pin "A") (pinfunction "A_A") (pintype "passive"))
      (node (ref "R1") (pin "1") (pinfunction "1_1") (pintype "passive"))
    )
    (net (code "34") (name "Net-(LED2-PadA)") (class "Default")
      (node (ref "LED2") (pin "A") (pinfunction "A_A") (pintype "passive"))
      (node (ref "R2") (pin "1") (pinfunction "1_1") (pintype "passive"))
    )
    (net (code "35") (name "Net-(LED3-PadA)") (class "Default")
      (node (ref "LED3") (pin "A") (pinfunction "A_A") (pintype "passive"))
      (node (ref "R3") (pin "1") (pinfunction "1_1") (pintype "passive"))
    )
    (net (code "36") (name "Net-(LED4-PadA)") (class "Default")
      (node (ref "LED4") (pin "A") (pinfunction "A_A") (pintype "passive"))
      (node (ref "R10") (pin "1") (pinfunction "1_1") (pintype "passive"))
    )
    (net (code "37") (name "Net-(LED5-PadA)") (class "Default")
      (node (ref "LED5") (pin "A") (pinfunction "A_A") (pintype "passive"))
      (node (ref "R8") (pin "2") (pinfunction "2_2") (pintype "passive"))
    )
    (net (code "38") (name "Net-(LED6-PadA)") (class "Default")
      (node (ref "LED6") (pin "A") (pinfunction "A_A") (pintype "passive"))
      (node (ref "R9") (pin "2") (pinfunction "2_2") (pintype "passive"))
    )
    (net (code "39") (name "Net-(OK1-A)") (class "Default")
      (node (ref "OK1") (pin "1") (pinfunction "A_1") (pintype "passive"))
      (node (ref "R12") (pin "2") (pinfunction "2_2") (pintype "passive"))
    )
    (net (code "40") (name "Net-(OK2-A)") (class "Default")
      (node (ref "OK2") (pin "1") (pinfunction "A_1") (pintype "passive"))
      (node (ref "R36") (pin "2") (pinfunction "2_2") (pintype "passive"))
    )
    (net (code "41") (name "Net-(Q1-D)") (class "Default")
      (node (ref "D3") (pin "C") (pinfunction "C_C") (pintype "passive"))
      (node (ref "Q1") (pin "3") (pinfunction "D_3") (pintype "passive"))
      (node (ref "R34") (pin "1") (pinfunction "1_1") (pintype "passive"))
    )
    (net (code "42") (name "Net-(Q1-G)") (class "Default")
      (node (ref "Q1") (pin "1") (pinfunction "G_1") (pintype "passive"))
      (node (ref "R35") (pin "2") (pinfunction "2_2") (pintype "passive"))
    )
    (net (code "43") (name "Net-(U$2-PB0(SS))") (class "Default")
      (node (ref "LED6") (pin "C") (pinfunction "C_C") (pintype "passive"))
      (node (ref "U$2") (pin "8") (pinfunction "PB0(SS)_8") (pintype "bidirectional"))
    )
    (net (code "44") (name "Net-(U$2-PD5)") (class "Default")
      (node (ref "LED5") (pin "C") (pinfunction "C_C") (pintype "passive"))
      (node (ref "U$2") (pin "22") (pinfunction "PD5_22") (pintype "bidirectional"))
    )
    (net (code "45") (name "Net-(U$2-UCAP)") (class "Default")
      (node (ref "C5") (pin "2") (pinfunction "2_2") (pintype "passive"))
      (node (ref "U$2") (pin "6") (pinfunction "UCAP_6") (pintype "bidirectional"))
    )
    (net (code "46") (name "Net-(U$2-XTAL1)") (class "Default")
      (node (ref "C6") (pin "2") (pinfunction "2_2") (pintype "passive"))
      (node (ref "R6") (pin "2") (pinfunction "2_2") (pintype "passive"))
      (node (ref "U$2") (pin "17") (pinfunction "XTAL1_17") (pintype "bidirectional"))
      (node (ref "Y1") (pin "2") (pinfunction "2_2") (pintype "passive"))
    )
    (net (code "47") (name "Net-(U$2-XTAL2)") (class "Default")
      (node (ref "C7") (pin "2") (pinfunction "2_2") (pintype "passive"))
      (node (ref "R6") (pin "1") (pinfunction "1_1") (pintype "passive"))
      (node (ref "U$2") (pin "16") (pinfunction "XTAL2_16") (pintype "bidirectional"))
      (node (ref "Y1") (pin "1") (pinfunction "1_1") (pintype "passive"))
    )
    (net (code "48") (name "Net-(U3-BAT)") (class "Default")
      (node (ref "D4") (pin "C") (pinfunction "C_C") (pintype "passive"))
      (node (ref "U3") (pin "20") (pinfunction "BAT_20") (pintype "power_in"))
    )
    (net (code "49") (name "Net-(U3-CAP1)") (class "Default")
      (node (ref "C10") (pin "1") (pinfunction "1_1") (pintype "passive"))
      (node (ref "U3") (pin "7") (pinfunction "CAP1_7") (pintype "output"))
    )
    (net (code "50") (name "Net-(U3-CAP2)") (class "Default")
      (node (ref "C11") (pin "2") (pinfunction "2_2") (pintype "passive"))
      (node (ref "U3") (pin "11") (pinfunction "NC_11_11") (pintype "passive"))
      (node (ref "U3") (pin "12") (pinfunction "NC_12_12") (pintype "passive"))
      (node (ref "U3") (pin "14") (pinfunction "CAP2_14") (pintype "output"))
    )
    (net (code "51") (name "Net-(U3-CAP3)") (class "Default")
      (node (ref "C12") (pin "2") (pinfunction "2_2") (pintype "passive"))
      (node (ref "U3") (pin "16") (pinfunction "NC_16_16") (pintype "passive"))
      (node (ref "U3") (pin "17") (pinfunction "NC_17_17") (pintype "passive"))
      (node (ref "U3") (pin "19") (pinfunction "CAP3_19") (pintype "output"))
    )
    (net (code "52") (name "Net-(U3-VC5X)") (class "Default")
      (node (ref "D6") (pin "C") (pinfunction "C_C") (pintype "passive"))
      (node (ref "U3") (pin "10") (pinfunction "VC5X_10") (pintype "power_in"))
    )
    (net (code "53") (name "Net-(U3-VC10X)") (class "Default")
      (node (ref "D5") (pin "C") (pinfunction "C_C") (pintype "passive"))
      (node (ref "U3") (pin "15") (pinfunction "VC10X_15") (pintype "power_in"))
    )
    (net (code "54") (name "Net-(U4-ADDR)") (class "Default")
      (node (ref "JP5") (pin "2") (pinfunction "2_2") (pintype "passive"))
      (node (ref "JP6") (pin "1") (pinfunction "1_1") (pintype "passive"))
      (node (ref "U4") (pin "1") (pinfunction "ADDR_1") (pintype "input"))
    )
    (net (code "55") (name "REGSRC") (class "Default")
      (node (ref "C30") (pin "1") (pinfunction "1_1") (pintype "passive"))
      (node (ref "Q1") (pin "2") (pinfunction "S_2") (pintype "passive"))
      (node (ref "U3") (pin "9") (pinfunction "REGSRC_9") (pintype "input"))
    )
    (net (code "56") (name "RST") (class "Default")
      (node (ref "C36") (pin "2") (pinfunction "2_2") (pintype "passive"))
      (node (ref "J8") (pin "5") (pinfunction "RESET_5") (pintype "passive"))
      (node (ref "R7") (pin "2") (pinfunction "2_2") (pintype "passive"))
      (node (ref "S1") (pin "1") (pinfunction "1_1") (pintype "passive"))
      (node (ref "S1") (pin "2") (pinfunction "2_2") (pintype "passive"))
      (node (ref "U$2") (pin "13") (pinfunction "~{RESET}_13") (pintype "bidirectional"))
    )
    (net (code "57") (name "RX") (class "Default")
      (node (ref "U$2") (pin "20") (pinfunction "PD2(RX)_20") (pintype "bidirectional"))
      (node (ref "U1") (pin "2") (pinfunction "RO_2") (pintype "output"))
    )
    (net (code "58") (name "RX_N") (class "Default")
      (node (ref "J1") (pin "4") (pinfunction "4_4") (pintype "passive"))
      (node (ref "U1") (pin "7") (pinfunction "B(R-)_7") (pintype "bidirectional"))
    )
    (net (code "59") (name "RX_P") (class "Default")
      (node (ref "J1") (pin "5") (pinfunction "5_5") (pintype "passive"))
      (node (ref "U1") (pin "8") (pinfunction "A(R+)_8") (pintype "bidirectional"))
    )
    (net (code "60") (name "SCK") (class "Default")
      (node (ref "J8") (pin "7") (pinfunction "SCK_7") (pintype "passive"))
      (node (ref "U$2") (pin "9") (pinfunction "PB1(SCK)_9") (pintype "bidirectional"))
    )
    (net (code "61") (name "SCL") (class "Default")
      (node (ref "R38") (pin "1") (pinfunction "1_1") (pintype "passive"))
      (node (ref "U$2") (pin "18") (pinfunction "PD0(SCL)_18") (pintype "bidirectional"))
      (node (ref "U4") (pin "10") (pinfunction "SCL_10") (pintype "input"))
      (node (ref "U5") (pin "3") (pinfunction "SCL1_3") (pintype "input"))
    )
    (net (code "62") (name "SCL_ISO") (class "Default")
      (node (ref "U3") (pin "5") (pinfunction "SCL_5") (pintype "input"))
      (node (ref "U5") (pin "6") (pinfunction "SCL2_6") (pintype "input"))
    )
    (net (code "63") (name "SDA") (class "Default")
      (node (ref "R39") (pin "1") (pinfunction "1_1") (pintype "passive"))
      (node (ref "U$2") (pin "19") (pinfunction "PD1(SDA)_19") (pintype "bidirectional"))
      (node (ref "U4") (pin "9") (pinfunction "SDA_9") (pintype "bidirectional"))
      (node (ref "U5") (pin "2") (pinfunction "SDA1_2") (pintype "bidirectional"))
    )
    (net (code "64") (name "SDA_ISO") (class "Default")
      (node (ref "U3") (pin "4") (pinfunction "SDA_4") (pintype "bidirectional"))
      (node (ref "U5") (pin "7") (pinfunction "SDA2_7") (pintype "bidirectional"))
    )
    (net (code "65") (name "TS1") (class "Default")
      (node (ref "J6") (pin "6") (pinfunction "6_6") (pintype "passive"))
      (node (ref "U$1") (pin "C") (pinfunction "C_C") (pintype "passive"))
      (node (ref "U3") (pin "6") (pinfunction "TS1_6") (pintype "input"))
    )
    (net (code "66") (name "TS2") (class "Default")
      (node (ref "J6") (pin "4") (pinfunction "4_4") (pintype "passive"))
      (node (ref "U3") (pin "13") (pinfunction "TS2_13") (pintype "input"))
    )
    (net (code "67") (name "TS3") (class "Default")
      (node (ref "J6") (pin "2") (pinfunction "2_2") (pintype "passive"))
      (node (ref "U3") (pin "18") (pinfunction "TS3_18") (pintype "input"))
    )
    (net (code "68") (name "TS4") (class "Default")
      (node (ref "J7") (pin "6") (pinfunction "6_6") (pintype "passive"))
      (node (ref "R40") (pin "2") (pinfunction "2_2") (pintype "passive"))
      (node (ref "U4") (pin "4") (pinfunction "AIN0_4") (pintype "input"))
    )
    (net (code "69") (name "TS5") (class "Default")
      (node (ref "J7") (pin "4") (pinfunction "4_4") (pintype "passive"))
      (node (ref "R41") (pin "2") (pinfunction "2_2") (pintype "passive"))
      (node (ref "U4") (pin "5") (pinfunction "AIN1_5") (pintype "input"))
    )
    (net (code "70") (name "TS6") (class "Default")
      (node (ref "J7") (pin "2") (pinfunction "2_2") (pintype "passive"))
      (node (ref "R42") (pin "2") (pinfunction "2_2") (pintype "passive"))
      (node (ref "U4") (pin "6") (pinfunction "AIN2_6") (pintype "input"))
    )
    (net (code "71") (name "TS_INTERNAL") (class "Default")
      (node (ref "J9") (pin "1") (pinfunction "1_1") (pintype "passive"))
      (node (ref "R43") (pin "2") (pinfunction "2_2") (pintype "passive"))
      (node (ref "U4") (pin "7") (pinfunction "AIN3_7") (pintype "input"))
    )
    (net (code "72") (name "TX") (class "Default")
      (node (ref "U$2") (pin "21") (pinfunction "PD3(TX)_21") (pintype "bidirectional"))
      (node (ref "U1") (pin "3") (pinfunction "DI_3") (pintype "input"))
    )
    (net (code "73") (name "TX_N") (class "Default")
      (node (ref "J1") (pin "3") (pinfunction "3_3") (pintype "passive"))
      (node (ref "U1") (pin "6") (pinfunction "Z(T-)_6") (pintype "bidirectional"))
    )
    (net (code "74") (name "TX_P") (class "Default")
      (node (ref "J1") (pin "2") (pinfunction "2_2") (pintype "passive"))
      (node (ref "U1") (pin "5") (pinfunction "Y(T+)_5") (pintype "bidirectional"))
    )
    (net (code "75") (name "USB_N") (class "Default")
      (node (ref "R4") (pin "2") (pinfunction "2_2") (pintype "passive"))
      (node (ref "U$2") (pin "3") (pinfunction "D-_3") (pintype "bidirectional"))
    )
    (net (code "76") (name "USB_P") (class "Default")
      (node (ref "R5") (pin "2") (pinfunction "2_2") (pintype "passive"))
      (node (ref "U$2") (pin "4") (pinfunction "D+_4") (pintype "bidirectional"))
    )
    (net (code "77") (name "UUSB_N") (class "Default")
      (node (ref "J2") (pin "2") (pinfunction "D-_2") (pintype "bidirectional"))
      (node (ref "R4") (pin "1") (pinfunction "1_1") (pintype "passive"))
    )
    (net (code "78") (name "UUSB_P") (class "Default")
      (node (ref "J2") (pin "3") (pinfunction "D+_3") (pintype "bidirectional"))
      (node (ref "R5") (pin "1") (pinfunction "1_1") (pintype "passive"))
    )
    (net (code "79") (name "VC0") (class "Default")
      (node (ref "C13") (pin "2") (pinfunction "2_2") (pintype "passive"))
      (node (ref "R13") (pin "2") (pinfunction "2_2") (pintype "passive"))
      (node (ref "U3") (pin "41") (pinfunction "VC0_41") (pintype "input"))
    )
    (net (code "80") (name "VC1") (class "Default")
      (node (ref "C13") (pin "1") (pinfunction "1_1") (pintype "passive"))
      (node (ref "C14") (pin "2") (pinfunction "2_2") (pintype "passive"))
      (node (ref "R14") (pin "2") (pinfunction "2_2") (pintype "passive"))
      (node (ref "U3") (pin "40") (pinfunction "VC1_40") (pintype "input"))
    )
    (net (code "81") (name "VC2") (class "Default")
      (node (ref "C14") (pin "1") (pinfunction "1_1") (pintype "passive"))
      (node (ref "C15") (pin "2") (pinfunction "2_2") (pintype "passive"))
      (node (ref "R15") (pin "2") (pinfunction "2_2") (pintype "passive"))
      (node (ref "U3") (pin "39") (pinfunction "VC2_39") (pintype "input"))
    )
    (net (code "82") (name "VC3") (class "Default")
      (node (ref "C15") (pin "1") (pinfunction "1_1") (pintype "passive"))
      (node (ref "C16") (pin "2") (pinfunction "2_2") (pintype "passive"))
      (node (ref "R16") (pin "2") (pinfunction "2_2") (pintype "passive"))
      (node (ref "U3") (pin "38") (pinfunction "VC3_38") (pintype "input"))
    )
    (net (code "83") (name "VC4") (class "Default")
      (node (ref "C16") (pin "1") (pinfunction "1_1") (pintype "passive"))
      (node (ref "C17") (pin "2") (pinfunction "2_2") (pintype "passive"))
      (node (ref "R17") (pin "2") (pinfunction "2_2") (pintype "passive"))
      (node (ref "U3") (pin "37") (pinfunction "VC4_37") (pintype "input"))
    )
    (net (code "84") (name "VC5") (class "Default")
      (node (ref "C17") (pin "1") (pinfunction "1_1") (pintype "passive"))
      (node (ref "R18") (pin "2") (pinfunction "2_2") (pintype "passive"))
      (node (ref "U3") (pin "36") (pinfunction "VC5_36") (pintype "input"))
    )
    (net (code "85") (name "VC5B") (class "Default")
      (node (ref "C18") (pin "1") (pinfunction "1_1") (pintype "passive"))
      (node (ref "R20") (pin "2") (pinfunction "2_2") (pintype "passive"))
      (node (ref "U3") (pin "35") (pinfunction "VC5B_35") (pintype "input"))
    )
    (net (code "86") (name "VC5X") (class "Default")
      (node (ref "C11") (pin "1") (pinfunction "1_1") (pintype "passive"))
      (node (ref "C12") (pin "1") (pinfunction "1_1") (pintype "passive"))
      (node (ref "C18") (pin "2") (pinfunction "2_2") (pintype "passive"))
      (node (ref "C19") (pin "2") (pinfunction "2_2") (pintype "passive"))
      (node (ref "C31") (pin "2") (pinfunction "2_2") (pintype "passive"))
      (node (ref "C33") (pin "1") (pinfunction "1_1") (pintype "passive"))
      (node (ref "D6") (pin "A") (pinfunction "A_A") (pintype "passive"))
      (node (ref "J6") (pin "3") (pinfunction "3_3") (pintype "passive"))
      (node (ref "R19") (pin "2") (pinfunction "2_2") (pintype "passive"))
      (node (ref "R35") (pin "1") (pinfunction "1_1") (pintype "passive"))
    )
    (net (code "87") (name "VC6") (class "Default")
      (node (ref "C19") (pin "1") (pinfunction "1_1") (pintype "passive"))
      (node (ref "C20") (pin "2") (pinfunction "2_2") (pintype "passive"))
      (node (ref "R21") (pin "2") (pinfunction "2_2") (pintype "passive"))
      (node (ref "U3") (pin "34") (pinfunction "VC6_34") (pintype "input"))
    )
    (net (code "88") (name "VC7") (class "Default")
      (node (ref "C20") (pin "1") (pinfunction "1_1") (pintype "passive"))
      (node (ref "C21") (pin "2") (pinfunction "2_2") (pintype "passive"))
      (node (ref "R22") (pin "2") (pinfunction "2_2") (pintype "passive"))
      (node (ref "U3") (pin "33") (pinfunction "VC7_33") (pintype "input"))
    )
    (net (code "89") (name "VC8") (class "Default")
      (node (ref "C21") (pin "1") (pinfunction "1_1") (pintype "passive"))
      (node (ref "C22") (pin "2") (pinfunction "2_2") (pintype "passive"))
      (node (ref "R23") (pin "2") (pinfunction "2_2") (pintype "passive"))
      (node (ref "U3") (pin "32") (pinfunction "VC8_32") (pintype "input"))
    )
    (net (code "90") (name "VC9") (class "Default")
      (node (ref "C22") (pin "1") (pinfunction "1_1") (pintype "passive"))
      (node (ref "C23") (pin "2") (pinfunction "2_2") (pintype "passive"))
      (node (ref "R24") (pin "2") (pinfunction "2_2") (pintype "passive"))
      (node (ref "U3") (pin "31") (pinfunction "VC9_31") (pintype "input"))
    )
    (net (code "91") (name "VC10") (class "Default")
      (node (ref "C23") (pin "1") (pinfunction "1_1") (pintype "passive"))
      (node (ref "R25") (pin "2") (pinfunction "2_2") (pintype "passive"))
      (node (ref "U3") (pin "30") (pinfunction "VC10_30") (pintype "input"))
    )
    (net (code "92") (name "VC10B") (class "Default")
      (node (ref "C24") (pin "1") (pinfunction "1_1") (pintype "passive"))
      (node (ref "R27") (pin "2") (pinfunction "2_2") (pintype "passive"))
      (node (ref "U3") (pin "29") (pinfunction "VC10B_29") (pintype "input"))
    )
    (net (code "93") (name "VC10X") (class "Default")
      (node (ref "C24") (pin "2") (pinfunction "2_2") (pintype "passive"))
      (node (ref "C25") (pin "2") (pinfunction "2_2") (pintype "passive"))
      (node (ref "C31") (pin "1") (pinfunction "1_1") (pintype "passive"))
      (node (ref "C32") (pin "2") (pinfunction "2_2") (pintype "passive"))
      (node (ref "D5") (pin "A") (pinfunction "A_A") (pintype "passive"))
      (node (ref "J6") (pin "1") (pinfunction "1_1") (pintype "passive"))
      (node (ref "R26") (pin "2") (pinfunction "2_2") (pintype "passive"))
    )
    (net (code "94") (name "VC11") (class "Default")
      (node (ref "C25") (pin "1") (pinfunction "1_1") (pintype "passive"))
      (node (ref "C26") (pin "2") (pinfunction "2_2") (pintype "passive"))
      (node (ref "R28") (pin "2") (pinfunction "2_2") (pintype "passive"))
      (node (ref "U3") (pin "28") (pinfunction "VC11_28") (pintype "input"))
    )
    (net (code "95") (name "VC12") (class "Default")
      (node (ref "C26") (pin "1") (pinfunction "1_1") (pintype "passive"))
      (node (ref "C27") (pin "2") (pinfunction "2_2") (pintype "passive"))
      (node (ref "R29") (pin "2") (pinfunction "2_2") (pintype "passive"))
      (node (ref "U3") (pin "27") (pinfunction "VC12_27") (pintype "input"))
    )
    (net (code "96") (name "VC13") (class "Default")
      (node (ref "C27") (pin "1") (pinfunction "1_1") (pintype "passive"))
      (node (ref "C28") (pin "2") (pinfunction "2_2") (pintype "passive"))
      (node (ref "R30") (pin "2") (pinfunction "2_2") (pintype "passive"))
      (node (ref "U3") (pin "26") (pinfunction "VC13_26") (pintype "input"))
    )
    (net (code "97") (name "VC14") (class "Default")
      (node (ref "C28") (pin "1") (pinfunction "1_1") (pintype "passive"))
      (node (ref "C29") (pin "2") (pinfunction "2_2") (pintype "passive"))
      (node (ref "R31") (pin "2") (pinfunction "2_2") (pintype "passive"))
      (node (ref "U3") (pin "25") (pinfunction "VC14_25") (pintype "input"))
    )
    (net (code "98") (name "VC15") (class "Default")
      (node (ref "C29") (pin "1") (pinfunction "1_1") (pintype "passive"))
      (node (ref "R32") (pin "2") (pinfunction "2_2") (pintype "passive"))
      (node (ref "U3") (pin "24") (pinfunction "VC15_24") (pintype "input"))
    )
    (net (code "99") (name "VCC-ISO") (class "Default")
      (node (ref "C35") (pin "1") (pinfunction "1_1") (pintype "passive"))
      (node (ref "OK2") (pin "4") (pinfunction "COL_4") (pintype "passive"))
      (node (ref "U3") (pin "8") (pinfunction "REGOUT_8") (pintype "power_in"))
      (node (ref "U5") (pin "8") (pinfunction "VCC2_8") (pintype "power_in"))
    )
    (net (code "100") (name "VIN") (class "Default")
      (node (ref "D1") (pin "A") (pinfunction "A_A") (pintype "passive"))
      (node (ref "J1") (pin "6") (pinfunction "6_6") (pintype "passive"))
      (node (ref "LED1") (pin "C") (pinfunction "C_C") (pintype "passive"))
    )
    (net (code "101") (name "V_BATT") (class "Default")
      (node (ref "C32") (pin "1") (pinfunction "1_1") (pintype "passive"))
      (node (ref "D4") (pin "A") (pinfunction "A_A") (pintype "passive"))
      (node (ref "JP9") (pin "2") (pinfunction "2_2") (pintype "passive"))
      (node (ref "R11") (pin "1") (pinfunction "1_1") (pintype "passive"))
    )
    (net (code "102") (name "V_USB") (class "Default")
      (node (ref "D2") (pin "A") (pinfunction "A_A") (pintype "passive"))
      (node (ref "J2") (pin "1") (pinfunction "VBUS_1") (pintype "power_in"))
      (node (ref "R10") (pin "2") (pinfunction "2_2") (pintype "passive"))
      (node (ref "U$2") (pin "7") (pinfunction "VBUS_7") (pintype "bidirectional"))
    )
    (net (code "103") (name "unconnected-(J2-ID-Pad4)") (class "Default")
      (node (ref "J2") (pin "4") (pinfunction "ID_4") (pintype "bidirectional"))
    )
    (net (code "104") (name "unconnected-(J8-NC-Pad3)") (class "Default")
      (node (ref "J8") (pin "3") (pinfunction "NC_3") (pintype "no_connect"))
    )
    (net (code "105") (name "unconnected-(U$2-AREF-Pad42)") (class "Default")
      (node (ref "U$2") (pin "42") (pinfunction "AREF_42") (pintype "bidirectional"))
    )
    (net (code "106") (name "unconnected-(U$2-PB5(ADC12)-Pad29)") (class "Default")
      (node (ref "U$2") (pin "29") (pinfunction "PB5(ADC12)_29") (pintype "bidirectional"))
    )
    (net (code "107") (name "unconnected-(U$2-PB7-Pad12)") (class "Default")
      (node (ref "U$2") (pin "12") (pinfunction "PB7_12") (pintype "bidirectional"))
    )
    (net (code "108") (name "unconnected-(U$2-PC6-Pad31)") (class "Default")
      (node (ref "U$2") (pin "31") (pinfunction "PC6_31") (pintype "bidirectional"))
    )
    (net (code "109") (name "unconnected-(U$2-PD4(ADC8)-Pad25)") (class "Default")
      (node (ref "U$2") (pin "25") (pinfunction "PD4(ADC8)_25") (pintype "bidirectional"))
    )
    (net (code "110") (name "unconnected-(U$2-PD6(ADC9)-Pad26)") (class "Default")
      (node (ref "U$2") (pin "26") (pinfunction "PD6(ADC9)_26") (pintype "bidirectional"))
    )
    (net (code "111") (name "unconnected-(U$2-PD7(ADC10)-Pad27)") (class "Default")
      (node (ref "U$2") (pin "27") (pinfunction "PD7(ADC10)_27") (pintype "bidirectional"))
    )
    (net (code "112") (name "unconnected-(U$2-PE2{slash}~{HWB}-Pad33)") (class "Default")
      (node (ref "U$2") (pin "33") (pinfunction "PE2/~{HWB}_33") (pintype "bidirectional"))
    )
    (net (code "113") (name "unconnected-(U$2-PE6-Pad1)") (class "Default")
      (node (ref "U$2") (pin "1") (pinfunction "PE6_1") (pintype "bidirectional"))
    )
    (net (code "114") (name "unconnected-(U$2-PF0(ADC0)-Pad41)") (class "Default")
      (node (ref "U$2") (pin "41") (pinfunction "PF0(ADC0)_41") (pintype "bidirectional"))
    )
    (net (code "115") (name "unconnected-(U$2-PF1(ADC1)-Pad40)") (class "Default")
      (node (ref "U$2") (pin "40") (pinfunction "PF1(ADC1)_40") (pintype "bidirectional"))
    )
    (net (code "116") (name "unconnected-(U$2-PF4(ADC4)-Pad39)") (class "Default")
      (node (ref "U$2") (pin "39") (pinfunction "PF4(ADC4)_39") (pintype "bidirectional"))
    )
    (net (code "117") (name "unconnected-(U$2-PF5(ADC5)-Pad38)") (class "Default")
      (node (ref "U$2") (pin "38") (pinfunction "PF5(ADC5)_38") (pintype "bidirectional"))
    )
    (net (code "118") (name "unconnected-(U$2-PF6(ADC6)-Pad37)") (class "Default")
      (node (ref "U$2") (pin "37") (pinfunction "PF6(ADC6)_37") (pintype "bidirectional"))
    )
    (net (code "119") (name "unconnected-(U$2-PF7(ADC7)-Pad36)") (class "Default")
      (node (ref "U$2") (pin "36") (pinfunction "PF7(ADC7)_36") (pintype "bidirectional"))
    )
    (net (code "120") (name "unconnected-(U3-NC_21-Pad21)") (class "Default")
      (node (ref "U3") (pin "21") (pinfunction "NC_21_21") (pintype "no_connect"))
    )
    (net (code "121") (name "unconnected-(U3-NC_22-Pad22)") (class "Default")
      (node (ref "U3") (pin "22") (pinfunction "NC_22_22") (pintype "no_connect"))
    )
    (net (code "122") (name "unconnected-(U3-NC_23-Pad23)") (class "Default")
      (node (ref "U3") (pin "23") (pinfunction "NC_23_23") (pintype "no_connect"))
    )
  )
)
